# switch_amp.net
KiCad netlist of a schematic drawn in Altium Designer
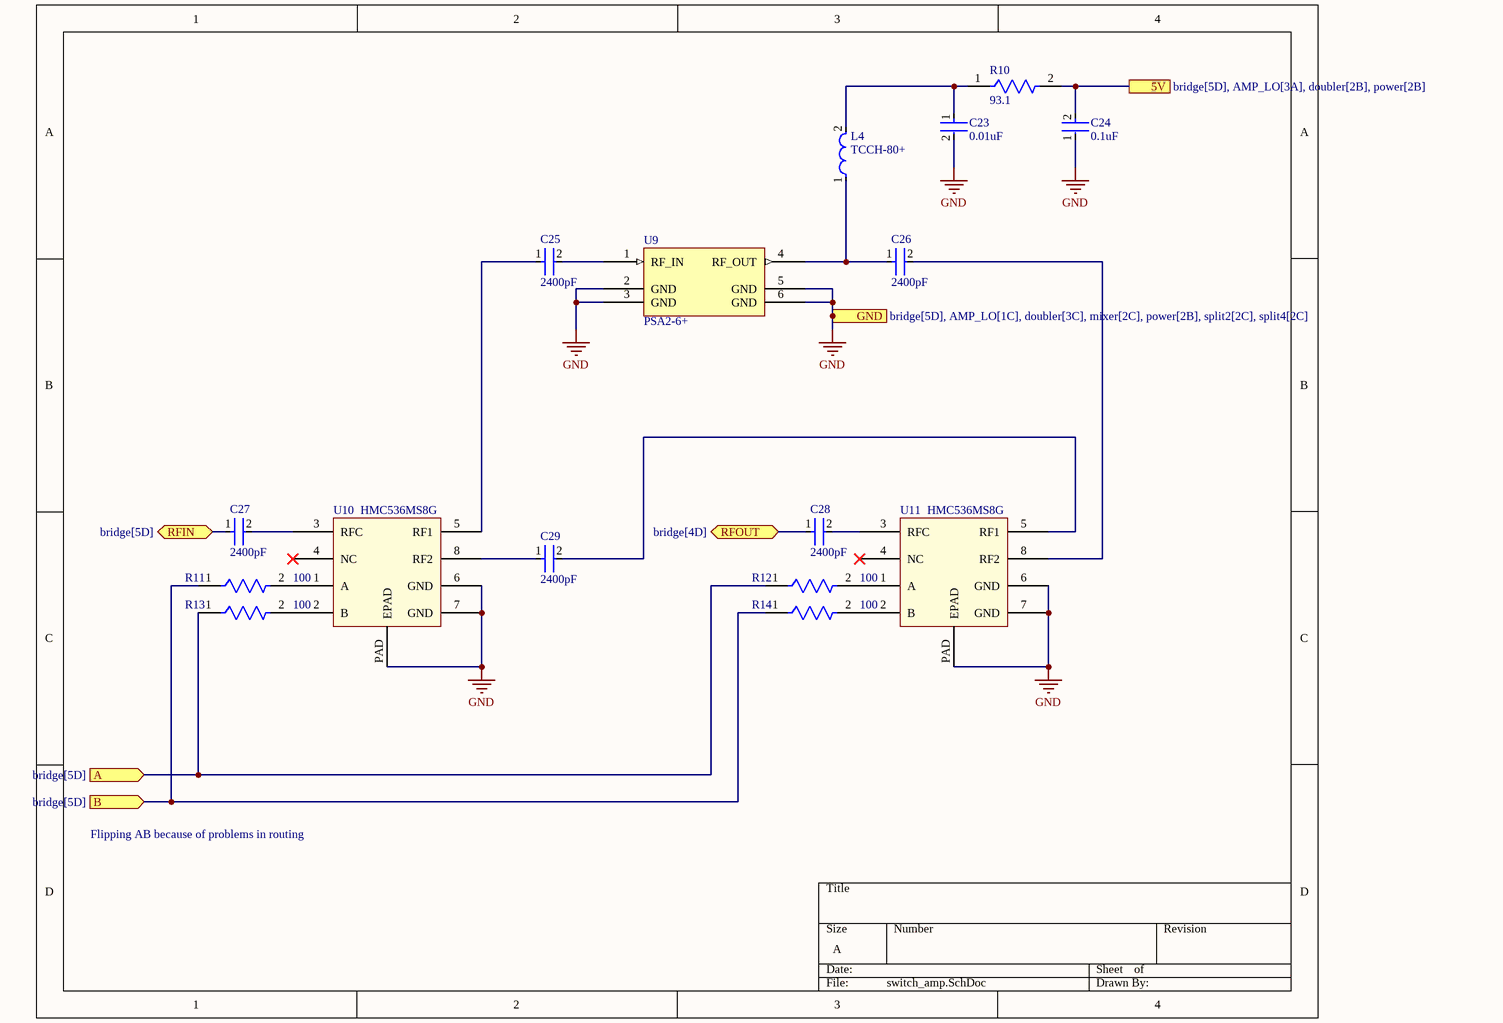
[diagram p0: switch_amp.SchDoc]

(export (version "E")
  (design (tool "Eeschema 10.0.6"))
  (components
    (comp (ref "C23")
      (value "0.01uF")
      (footprint "FP-GRM188-0_1-e0_2_0_5-IPC_B")
      (fields (field (name "VOLTAGE") "50V") (field (name "TOLERANCE") "5%"))
      (libsource (lib "Altium Content Vault") (part "11868f565c42a9108669ba33697ecf6"))
    )
    (comp (ref "C24")
      (value "0.1uF")
      (footprint "FP-GCJ188-0_2-IPC_C")
      (fields (field (name "TOLERANCE") "10%"))
      (libsource (lib "Altium Content Vault") (part "f23184f103b6ebe33a8c269c53dcba6"))
    )
    (comp (ref "C25")
      (value "2400pF")
      (footprint "FP-GRM188-0_1-e0_2_0_5-MFG")
      (fields (field (name "TOLERANCE") "5%") (field (name "VOLTAGE") "50V"))
      (libsource (lib "Altium Content Vault") (part "11868f565c42a9108669ba33697ecf6"))
    )
    (comp (ref "C26")
      (value "2400pF")
      (footprint "FP-GRM188-0_1-e0_2_0_5-MFG")
      (fields (field (name "TOLERANCE") "5%") (field (name "VOLTAGE") "50V"))
      (libsource (lib "Altium Content Vault") (part "11868f565c42a9108669ba33697ecf6"))
    )
    (comp (ref "C27")
      (value "2400pF")
      (footprint "FP-GRM188-0_1-e0_2_0_5-MFG")
      (fields (field (name "TOLERANCE") "5%") (field (name "VOLTAGE") "50V"))
      (libsource (lib "Altium Content Vault") (part "11868f565c42a9108669ba33697ecf6"))
    )
    (comp (ref "C28")
      (value "2400pF")
      (footprint "FP-GRM188-0_1-e0_2_0_5-MFG")
      (fields (field (name "TOLERANCE") "5%") (field (name "VOLTAGE") "50V"))
      (libsource (lib "Altium Content Vault") (part "11868f565c42a9108669ba33697ecf6"))
    )
    (comp (ref "C29")
      (value "2400pF")
      (footprint "FP-GRM188-0_1-e0_2_0_5-MFG")
      (fields (field (name "TOLERANCE") "5%") (field (name "VOLTAGE") "50V"))
      (libsource (lib "Altium Content Vault") (part "11868f565c42a9108669ba33697ecf6"))
    )
    (comp (ref "L4")
      (value "TCCH-80+")
      (footprint "FP-IFSC1515AH-MFG")
      (description "FIXED IND 4UH 200MA 100MOHM SMD")
      (fields
        (field (name "MANUFACTURER") "Vishay")
        (field (name "MANUFACTURER PART NUMBER") "IFSC1515AHER470M01")
      )
      (libsource (lib "Altium Content Vault") (part "725321dda6339637d4d059423bc1c3c"))
    )
    (comp (ref "R10")
      (value "93.1")
      (footprint "FP-CRCW0805-e3-MFG")
      (description "CRCW080593R1FKEA; RES Thick Film, 93.1Ω, 1%, 0.125W, 100ppm/°C, 0805")
      (fields (field (name "TOLERANCE") "1%"))
      (libsource (lib "Altium Content Vault") (part "1029c3af85768c4190bb7ad29bc67b5"))
    )
    (comp (ref "R11")
      (value "100")
      (footprint "FP-RC0603-0_55-MFG")
      (description "RES SMD 100 OHM 5% 1/10W 0603")
      (fields (field (name "TOLERANCE") "5%"))
      (libsource (lib "Altium Content Vault") (part "1029c3af85768c4190bb7ad29bc67b5"))
    )
    (comp (ref "R12")
      (value "100")
      (footprint "FP-RC0603-0_55-MFG")
      (description "RES SMD 100 OHM 5% 1/10W 0603")
      (fields (field (name "TOLERANCE") "5%"))
      (libsource (lib "Altium Content Vault") (part "1029c3af85768c4190bb7ad29bc67b5"))
    )
    (comp (ref "R13")
      (value "100")
      (footprint "FP-RC0603-0_55-MFG")
      (description "RES SMD 100 OHM 5% 1/10W 0603")
      (fields (field (name "TOLERANCE") "5%"))
      (libsource (lib "Altium Content Vault") (part "1029c3af85768c4190bb7ad29bc67b5"))
    )
    (comp (ref "R14")
      (value "100")
      (footprint "FP-RC0603-0_55-MFG")
      (description "RES SMD 100 OHM 5% 1/10W 0603")
      (fields (field (name "TOLERANCE") "5%"))
      (libsource (lib "Altium Content Vault") (part "1029c3af85768c4190bb7ad29bc67b5"))
    )
    (comp (ref "U9")
      (value "PSA2-6+")
      (footprint "PSA2-6+ SOT-363")
      (description "SMT MMIC, Linear, Gain Block Amplifier, DC to 7000 MHz, 50Ω, SOT-363 Style Package")
      (libsource (lib "FullyDigital") (part "PSA2-6+"))
    )
    (comp (ref "U10")
      (value "HMC536MS8G")
      (footprint "RH_8_1_ADI")
      (description "RF Switch ICs 3 Watt SPDT T/R Switch SMT, DC - 6 GHz")
      (libsource (lib "FullyDigital") (part "HMC536MS8G"))
    )
    (comp (ref "U11")
      (value "HMC536MS8G")
      (footprint "RH_8_1_ADI")
      (description "RF Switch ICs 3 Watt SPDT T/R Switch SMT, DC - 6 GHz")
      (libsource (lib "FullyDigital") (part "HMC536MS8G"))
    )
  )
  (nets
    (net (code "1") (name "/5V") (class "Default")
      (node (ref "C24") (pin "2") (pinfunction "2_2") (pintype "passive"))
      (node (ref "R10") (pin "2") (pinfunction "2_2") (pintype "passive"))
    )
    (net (code "2") (name "/A") (class "Default")
      (node (ref "R12") (pin "1") (pinfunction "1_1") (pintype "passive"))
      (node (ref "R13") (pin "1") (pinfunction "1_1") (pintype "passive"))
    )
    (net (code "3") (name "/B") (class "Default")
      (node (ref "R11") (pin "1") (pinfunction "1_1") (pintype "passive"))
      (node (ref "R14") (pin "1") (pinfunction "1_1") (pintype "passive"))
    )
    (net (code "4") (name "/RFIN") (class "Default")
      (node (ref "C27") (pin "1") (pinfunction "1_1") (pintype "passive"))
    )
    (net (code "5") (name "/RFOUT") (class "Default")
      (node (ref "C28") (pin "1") (pinfunction "1_1") (pintype "passive"))
    )
    (net (code "6") (name "GND") (class "Default")
      (node (ref "C23") (pin "2") (pinfunction "2_2") (pintype "passive"))
      (node (ref "C24") (pin "1") (pinfunction "1_1") (pintype "passive"))
      (node (ref "U10") (pin "6") (pinfunction "GND_6") (pintype "passive"))
      (node (ref "U10") (pin "7") (pinfunction "GND_7") (pintype "passive"))
      (node (ref "U10") (pin "PAD") (pinfunction "EPAD_PAD") (pintype "passive"))
      (node (ref "U11") (pin "6") (pinfunction "GND_6") (pintype "passive"))
      (node (ref "U11") (pin "7") (pinfunction "GND_7") (pintype "passive"))
      (node (ref "U11") (pin "PAD") (pinfunction "EPAD_PAD") (pintype "passive"))
      (node (ref "U9") (pin "2") (pinfunction "GND_2") (pintype "passive"))
      (node (ref "U9") (pin "3") (pinfunction "GND_3") (pintype "passive"))
      (node (ref "U9") (pin "5") (pinfunction "GND_5") (pintype "passive"))
      (node (ref "U9") (pin "6") (pinfunction "GND_6") (pintype "passive"))
    )
    (net (code "7") (name "Net-(C23-Pad1)") (class "Default")
      (node (ref "C23") (pin "1") (pinfunction "1_1") (pintype "passive"))
      (node (ref "L4") (pin "2") (pinfunction "2_2") (pintype "passive"))
      (node (ref "R10") (pin "1") (pinfunction "1_1") (pintype "passive"))
    )
    (net (code "8") (name "Net-(U9-RF_IN)") (class "Default")
      (node (ref "C25") (pin "2") (pinfunction "2_2") (pintype "passive"))
      (node (ref "U9") (pin "1") (pinfunction "RF_IN_1") (pintype "input"))
    )
    (net (code "9") (name "Net-(U9-RF_OUT)") (class "Default")
      (node (ref "C26") (pin "1") (pinfunction "1_1") (pintype "passive"))
      (node (ref "L4") (pin "1") (pinfunction "1_1") (pintype "passive"))
      (node (ref "U9") (pin "4") (pinfunction "RF_OUT_4") (pintype "output"))
    )
    (net (code "10") (name "Net-(U10-A)") (class "Default")
      (node (ref "R11") (pin "2") (pinfunction "2_2") (pintype "passive"))
      (node (ref "U10") (pin "1") (pinfunction "A_1") (pintype "passive"))
    )
    (net (code "11") (name "Net-(U10-B)") (class "Default")
      (node (ref "R13") (pin "2") (pinfunction "2_2") (pintype "passive"))
      (node (ref "U10") (pin "2") (pinfunction "B_2") (pintype "passive"))
    )
    (net (code "12") (name "Net-(U10-RF1)") (class "Default")
      (node (ref "C25") (pin "1") (pinfunction "1_1") (pintype "passive"))
      (node (ref "U10") (pin "5") (pinfunction "RF1_5") (pintype "passive"))
    )
    (net (code "13") (name "Net-(U10-RF2)") (class "Default")
      (node (ref "C29") (pin "1") (pinfunction "1_1") (pintype "passive"))
      (node (ref "U10") (pin "8") (pinfunction "RF2_8") (pintype "passive"))
    )
    (net (code "14") (name "Net-(U10-RFC)") (class "Default")
      (node (ref "C27") (pin "2") (pinfunction "2_2") (pintype "passive"))
      (node (ref "U10") (pin "3") (pinfunction "RFC_3") (pintype "passive"))
    )
    (net (code "15") (name "Net-(U11-A)") (class "Default")
      (node (ref "R12") (pin "2") (pinfunction "2_2") (pintype "passive"))
      (node (ref "U11") (pin "1") (pinfunction "A_1") (pintype "passive"))
    )
    (net (code "16") (name "Net-(U11-B)") (class "Default")
      (node (ref "R14") (pin "2") (pinfunction "2_2") (pintype "passive"))
      (node (ref "U11") (pin "2") (pinfunction "B_2") (pintype "passive"))
    )
    (net (code "17") (name "Net-(U11-RF1)") (class "Default")
      (node (ref "C29") (pin "2") (pinfunction "2_2") (pintype "passive"))
      (node (ref "U11") (pin "5") (pinfunction "RF1_5") (pintype "passive"))
    )
    (net (code "18") (name "Net-(U11-RF2)") (class "Default")
      (node (ref "C26") (pin "2") (pinfunction "2_2") (pintype "passive"))
      (node (ref "U11") (pin "8") (pinfunction "RF2_8") (pintype "passive"))
    )
    (net (code "19") (name "Net-(U11-RFC)") (class "Default")
      (node (ref "C28") (pin "2") (pinfunction "2_2") (pintype "passive"))
      (node (ref "U11") (pin "3") (pinfunction "RFC_3") (pintype "passive"))
    )
    (net (code "20") (name "unconnected-(U10-NC-Pad4)") (class "Default")
      (node (ref "U10") (pin "4") (pinfunction "NC_4") (pintype "passive+no_connect"))
    )
    (net (code "21") (name "unconnected-(U11-NC-Pad4)") (class "Default")
      (node (ref "U11") (pin "4") (pinfunction "NC_4") (pintype "passive+no_connect"))
    )
  )
)
